# 09_-_DISPLAY.net
KiCad netlist of a schematic drawn in Altium Designer
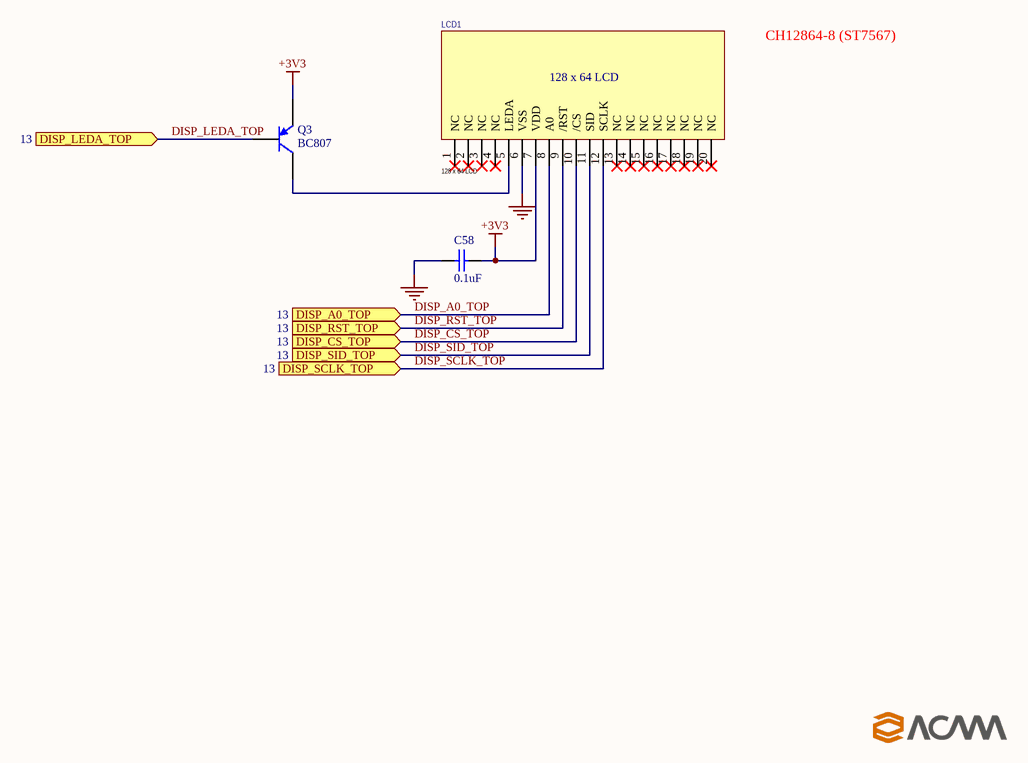
[diagram p0: [09] - DISPLAY.SchDoc]

(export (version "E")
  (design (tool "Eeschema 10.0.6"))
  (components
    (comp (ref "C58")
      (value "0.1uF")
      (footprint "0805_C_AUTO")
      (description "Non-Pol SMD Capacitor")
      (libsource (lib "Farzan Custom Library") (part "Cap SMD"))
    )
    (comp (ref "LCD1")
      (value "128 x 64 LCD")
      (footprint "LCD_128x64")
      (description "Chiness 128 x 64 LCD")
      (libsource (lib "Sub Board Top") (part "LCD 128x64"))
    )
    (comp (ref "Q3")
      (value "BC807")
      (footprint "SOT23")
      (description "PNP General Purpose Transistor")
      (libsource (lib "Farzan Custom Library") (part "Transistor PNP"))
    )
  )
  (nets
    (net (code "1") (name "+3V3") (class "Default")
      (node (ref "C58") (pin "1") (pinfunction "1_1") (pintype "passive"))
      (node (ref "LCD1") (pin "7") (pinfunction "VDD_7") (pintype "power_in"))
      (node (ref "Q3") (pin "2") (pinfunction "E_2") (pintype "passive"))
    )
    (net (code "2") (name "/DISP_A0_TOP") (class "Default")
      (node (ref "LCD1") (pin "8") (pinfunction "A0_8") (pintype "passive"))
    )
    (net (code "3") (name "/DISP_CS_TOP") (class "Default")
      (node (ref "LCD1") (pin "10") (pinfunction "/CS_10") (pintype "passive"))
    )
    (net (code "4") (name "/DISP_LEDA_TOP") (class "Default")
      (node (ref "Q3") (pin "1") (pinfunction "B_1") (pintype "passive"))
    )
    (net (code "5") (name "/DISP_RST_TOP") (class "Default")
      (node (ref "LCD1") (pin "9") (pinfunction "/RST_9") (pintype "passive"))
    )
    (net (code "6") (name "/DISP_SCLK_TOP") (class "Default")
      (node (ref "LCD1") (pin "12") (pinfunction "SCLK_12") (pintype "passive"))
    )
    (net (code "7") (name "/DISP_SID_TOP") (class "Default")
      (node (ref "LCD1") (pin "11") (pinfunction "SID_11") (pintype "passive"))
    )
    (net (code "8") (name "GND") (class "Default")
      (node (ref "C58") (pin "2") (pinfunction "2_2") (pintype "passive"))
      (node (ref "LCD1") (pin "6") (pinfunction "VSS_6") (pintype "power_in"))
    )
    (net (code "9") (name "Net-(LCD1-LEDA)") (class "Default")
      (node (ref "LCD1") (pin "5") (pinfunction "LEDA_5") (pintype "passive"))
      (node (ref "Q3") (pin "3") (pinfunction "C_3") (pintype "passive"))
    )
    (net (code "10") (name "unconnected-(LCD1-NC-Pad1)") (class "Default")
      (node (ref "LCD1") (pin "1") (pinfunction "NC_1") (pintype "passive+no_connect"))
    )
    (net (code "11") (name "unconnected-(LCD1-NC-Pad2)") (class "Default")
      (node (ref "LCD1") (pin "2") (pinfunction "NC_2") (pintype "passive+no_connect"))
    )
    (net (code "12") (name "unconnected-(LCD1-NC-Pad3)") (class "Default")
      (node (ref "LCD1") (pin "3") (pinfunction "NC_3") (pintype "passive+no_connect"))
    )
    (net (code "13") (name "unconnected-(LCD1-NC-Pad4)") (class "Default")
      (node (ref "LCD1") (pin "4") (pinfunction "NC_4") (pintype "passive+no_connect"))
    )
    (net (code "14") (name "unconnected-(LCD1-NC-Pad13)") (class "Default")
      (node (ref "LCD1") (pin "13") (pinfunction "NC_13") (pintype "passive+no_connect"))
    )
    (net (code "15") (name "unconnected-(LCD1-NC-Pad14)") (class "Default")
      (node (ref "LCD1") (pin "14") (pinfunction "NC_14") (pintype "passive+no_connect"))
    )
    (net (code "16") (name "unconnected-(LCD1-NC-Pad15)") (class "Default")
      (node (ref "LCD1") (pin "15") (pinfunction "NC_15") (pintype "passive+no_connect"))
    )
    (net (code "17") (name "unconnected-(LCD1-NC-Pad16)") (class "Default")
      (node (ref "LCD1") (pin "16") (pinfunction "NC_16") (pintype "passive+no_connect"))
    )
    (net (code "18") (name "unconnected-(LCD1-NC-Pad17)") (class "Default")
      (node (ref "LCD1") (pin "17") (pinfunction "NC_17") (pintype "passive+no_connect"))
    )
    (net (code "19") (name "unconnected-(LCD1-NC-Pad18)") (class "Default")
      (node (ref "LCD1") (pin "18") (pinfunction "NC_18") (pintype "passive+no_connect"))
    )
    (net (code "20") (name "unconnected-(LCD1-NC-Pad19)") (class "Default")
      (node (ref "LCD1") (pin "19") (pinfunction "NC_19") (pintype "passive+no_connect"))
    )
    (net (code "21") (name "unconnected-(LCD1-NC-Pad20)") (class "Default")
      (node (ref "LCD1") (pin "20") (pinfunction "NC_20") (pintype "passive+no_connect"))
    )
  )
)
